# PhotonOnAStick-V3.net
KiCad netlist of a schematic drawn in EAGLE
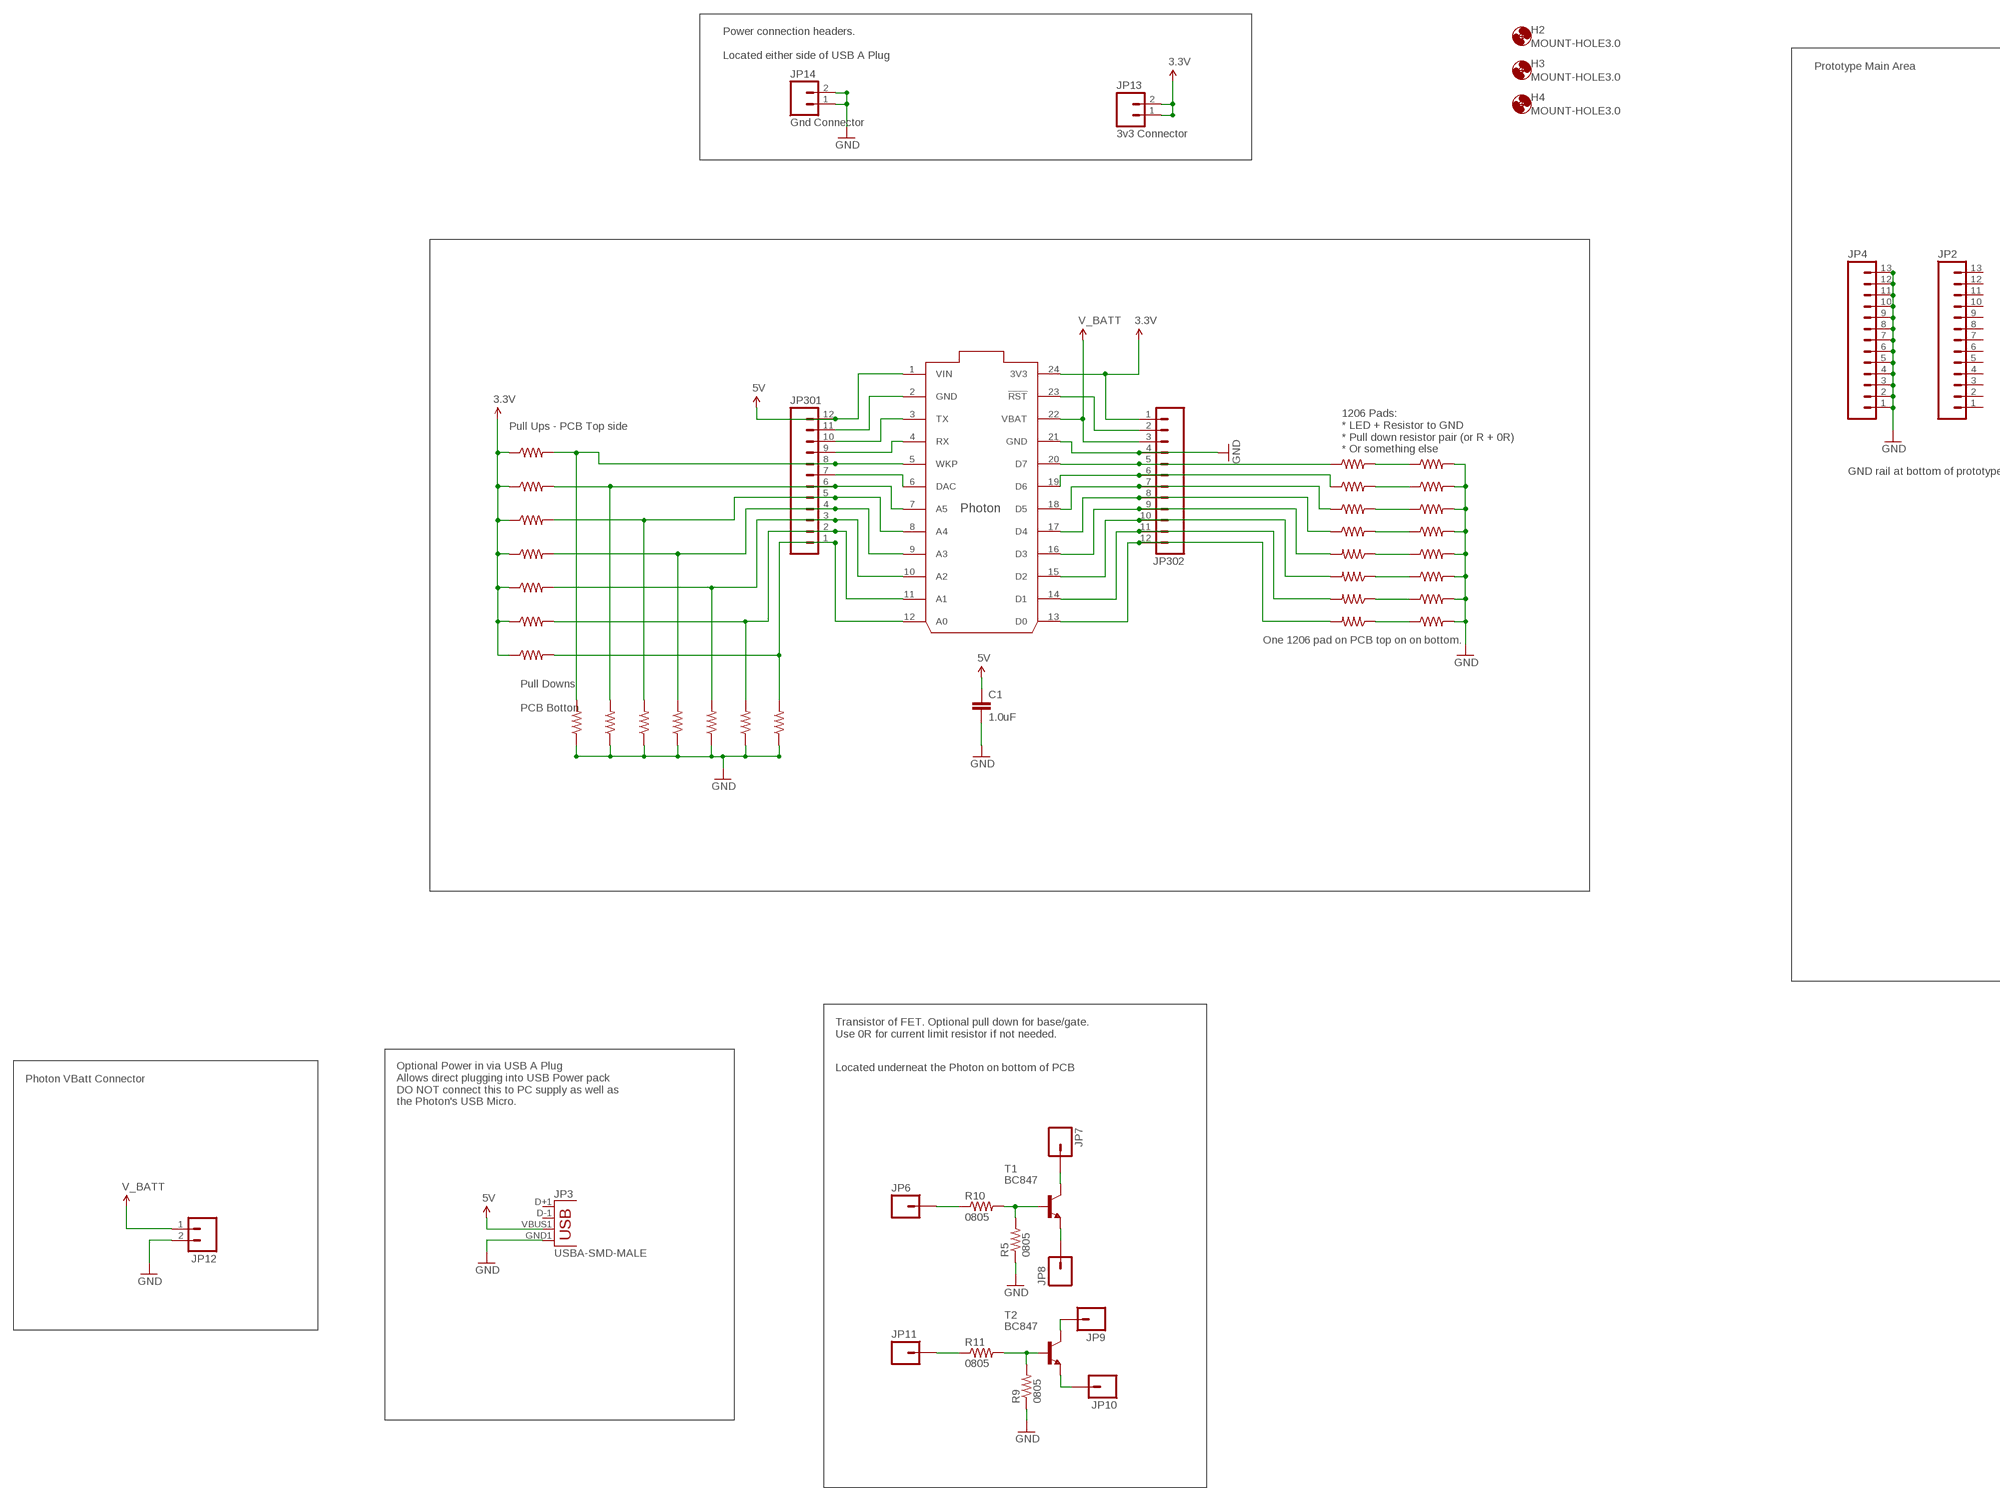
[diagram p0: schematic, sheet 1, part 1 of 2]
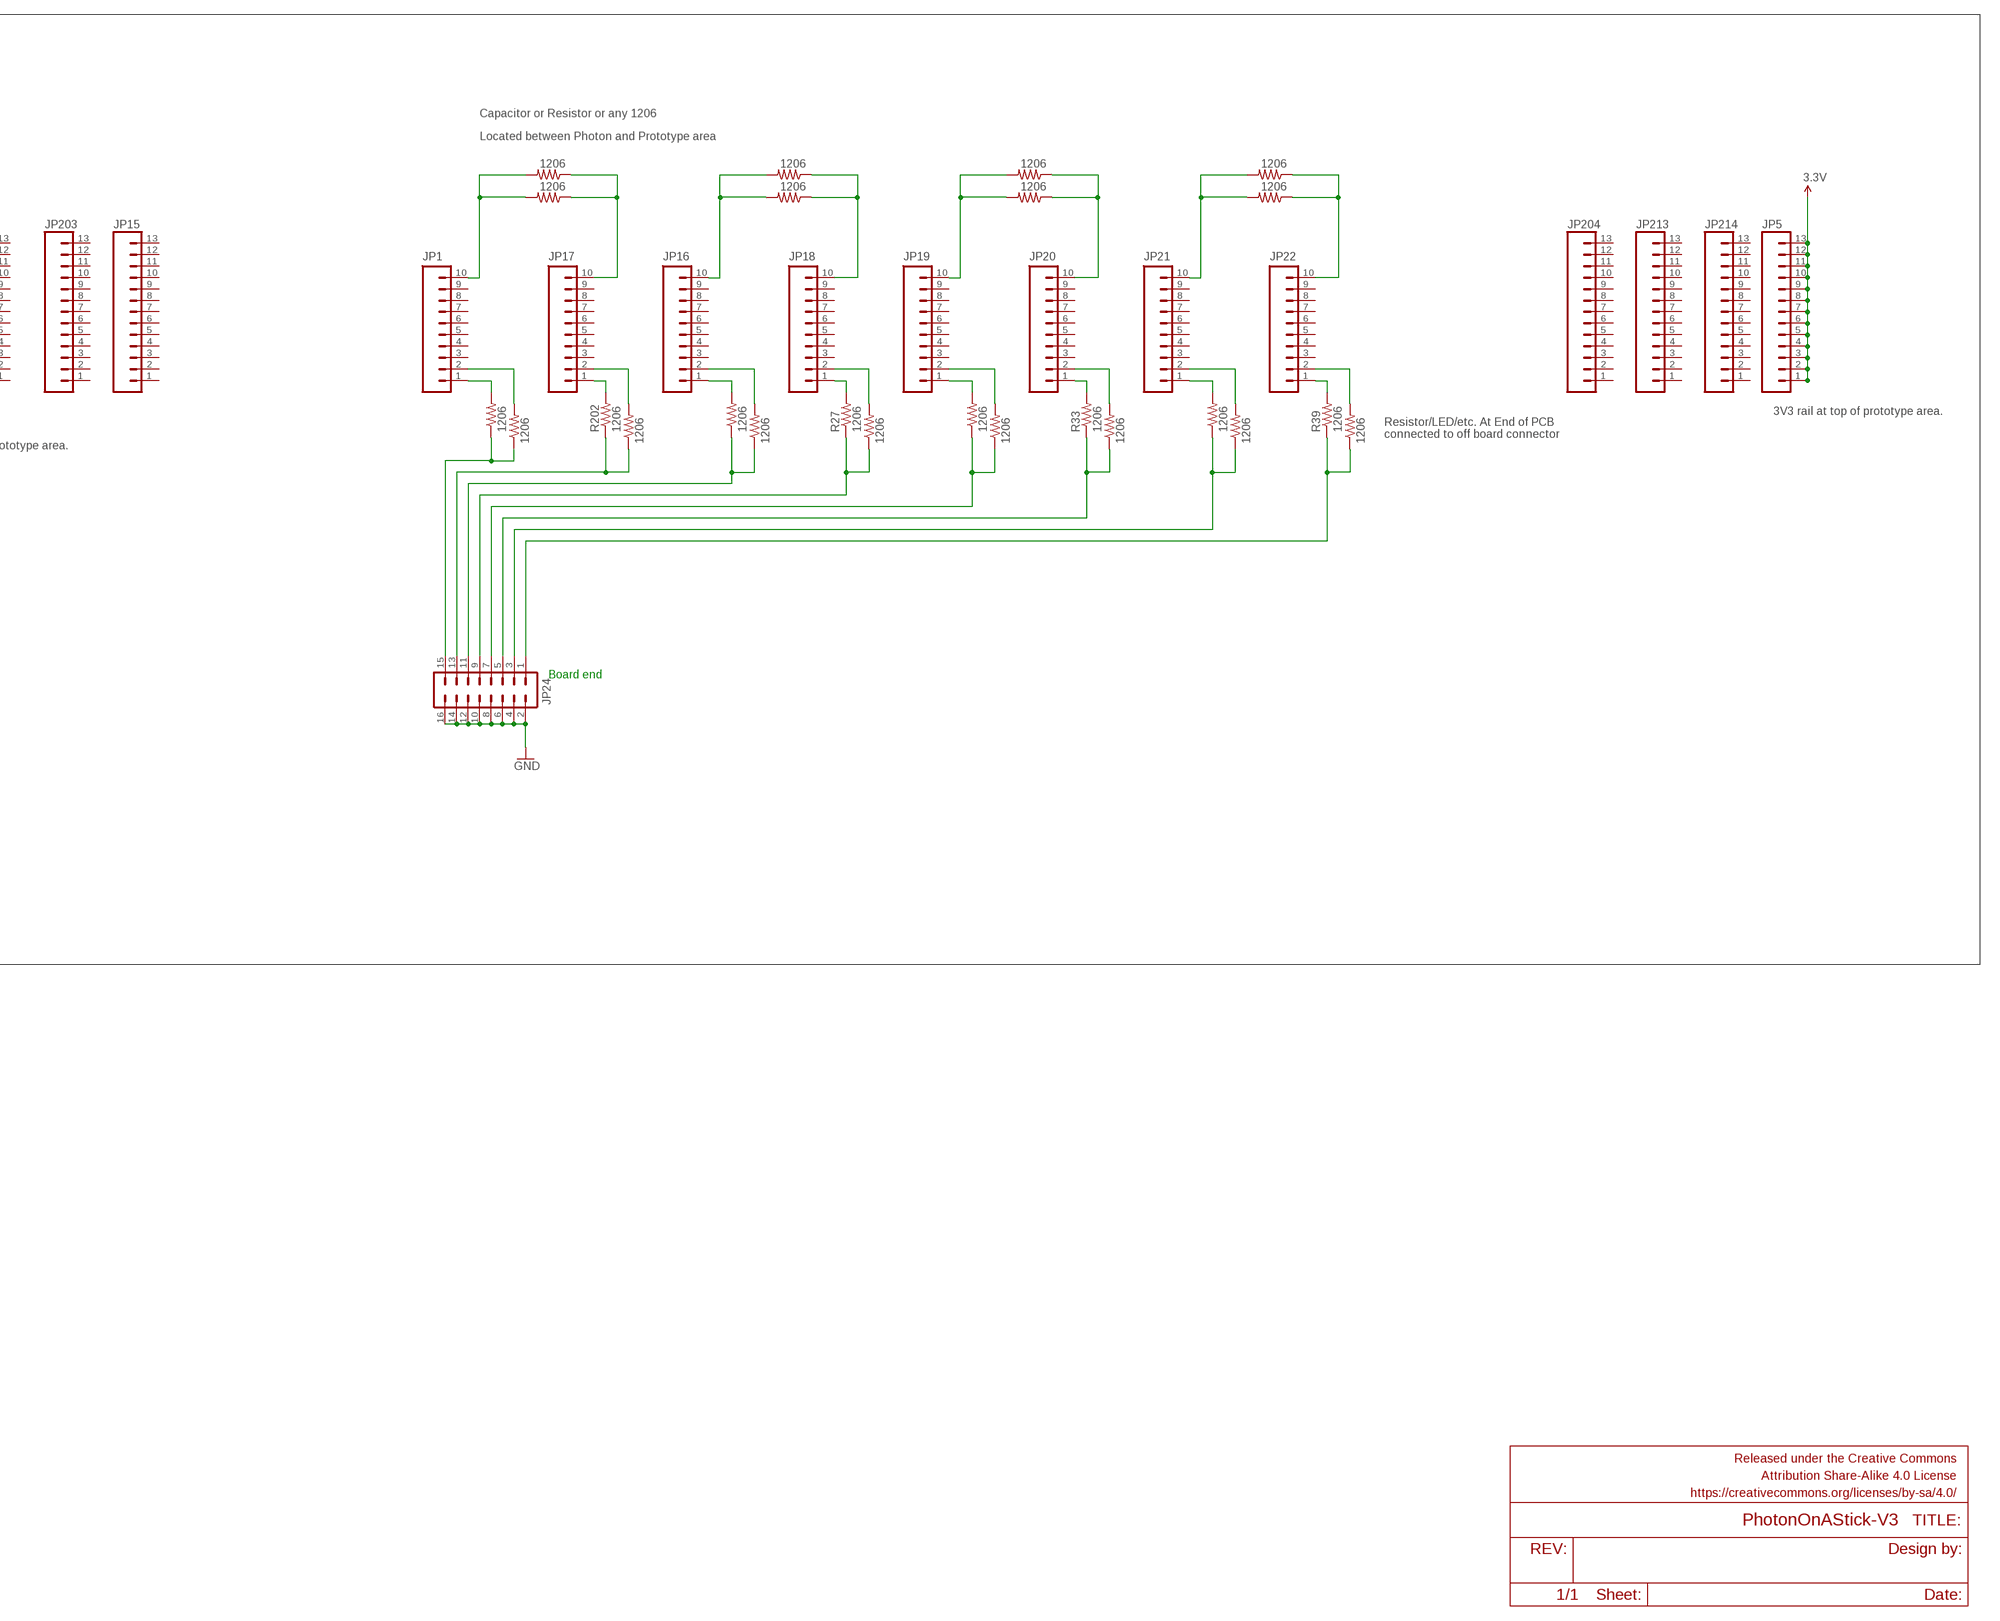
[diagram p1: schematic, sheet 1, part 2 of 2]

(export (version "E")
  (design (tool "Eeschema 10.0.6"))
  (components
    (comp (ref "C1")
      (value "1.0uF")
      (footprint "eagle-import:0805-CAP")
      (libsource (lib "eagle-import") (part "1.0UF-25V-+80/-20(0805){dblquote}"))
    )
    (comp (ref "FRAME1")
      (value "FRAME-LEDGER")
      (footprint "eagle-import:CREATIVE_COMMONS")
      (libsource (lib "eagle-import") (part "FRAME-LEDGER"))
    )
    (comp (ref "H2")
      (value "MOUNT-HOLE3.0")
      (footprint "eagle-import:3,0")
      (libsource (lib "eagle-import") (part "MOUNT-HOLE3.0"))
    )
    (comp (ref "H3")
      (value "MOUNT-HOLE3.0")
      (footprint "eagle-import:3,0")
      (libsource (lib "eagle-import") (part "MOUNT-HOLE3.0"))
    )
    (comp (ref "H4")
      (value "MOUNT-HOLE3.0")
      (footprint "eagle-import:3,0")
      (libsource (lib "eagle-import") (part "MOUNT-HOLE3.0"))
    )
    (comp (ref "IC1")
      (value "PHOTON_WITH_HEADERS")
      (footprint "eagle-import:PHOTON")
      (libsource (lib "eagle-import") (part "PHOTON_WITH_HEADERS"))
    )
    (comp (ref "JP1")
      (value "M10SILK_FEMALE_PTH")
      (footprint "eagle-import:1X10")
      (libsource (lib "eagle-import") (part "M10SILK_FEMALE_PTH"))
    )
    (comp (ref "JP2")
      (value "M13")
      (footprint "eagle-import:1X13")
      (libsource (lib "eagle-import") (part "M13"))
    )
    (comp (ref "JP3")
      (value "USBA-SMD-MALE")
      (footprint "eagle-import:USB-A-SMT-MALE")
      (libsource (lib "eagle-import") (part "USBA-SMD-MALE"))
    )
    (comp (ref "JP4")
      (value "M13")
      (footprint "eagle-import:1X13")
      (libsource (lib "eagle-import") (part "M13"))
    )
    (comp (ref "JP5")
      (value "M13")
      (footprint "eagle-import:1X13")
      (libsource (lib "eagle-import") (part "M13"))
    )
    (comp (ref "JP6")
      (value "M01PTH")
      (footprint "eagle-import:1X01")
      (libsource (lib "eagle-import") (part "M01PTH"))
    )
    (comp (ref "JP7")
      (value "M01PTH")
      (footprint "eagle-import:1X01")
      (libsource (lib "eagle-import") (part "M01PTH"))
    )
    (comp (ref "JP8")
      (value "M01PTH")
      (footprint "eagle-import:1X01")
      (libsource (lib "eagle-import") (part "M01PTH"))
    )
    (comp (ref "JP9")
      (value "M01PTH")
      (footprint "eagle-import:1X01")
      (libsource (lib "eagle-import") (part "M01PTH"))
    )
    (comp (ref "JP10")
      (value "M01PTH")
      (footprint "eagle-import:1X01")
      (libsource (lib "eagle-import") (part "M01PTH"))
    )
    (comp (ref "JP11")
      (value "M01PTH")
      (footprint "eagle-import:1X01")
      (libsource (lib "eagle-import") (part "M01PTH"))
    )
    (comp (ref "JP12")
      (value "M02JST-PTH-2")
      (footprint "eagle-import:JST-2-PTH")
      (libsource (lib "eagle-import") (part "M02JST-PTH-2"))
    )
    (comp (ref "JP13")
      (value "3v3 Connector")
      (footprint "eagle-import:1X02")
      (libsource (lib "eagle-import") (part "M02PTH"))
    )
    (comp (ref "JP14")
      (value "Gnd Connector")
      (footprint "eagle-import:1X02")
      (libsource (lib "eagle-import") (part "M02PTH"))
    )
    (comp (ref "JP15")
      (value "M13")
      (footprint "eagle-import:1X13")
      (libsource (lib "eagle-import") (part "M13"))
    )
    (comp (ref "JP16")
      (value "M10SILK_FEMALE_PTH")
      (footprint "eagle-import:1X10")
      (libsource (lib "eagle-import") (part "M10SILK_FEMALE_PTH"))
    )
    (comp (ref "JP17")
      (value "M10SILK_FEMALE_PTH")
      (footprint "eagle-import:1X10")
      (libsource (lib "eagle-import") (part "M10SILK_FEMALE_PTH"))
    )
    (comp (ref "JP18")
      (value "M10SILK_FEMALE_PTH")
      (footprint "eagle-import:1X10")
      (libsource (lib "eagle-import") (part "M10SILK_FEMALE_PTH"))
    )
    (comp (ref "JP19")
      (value "M10SILK_FEMALE_PTH")
      (footprint "eagle-import:1X10")
      (libsource (lib "eagle-import") (part "M10SILK_FEMALE_PTH"))
    )
    (comp (ref "JP20")
      (value "M10SILK_FEMALE_PTH")
      (footprint "eagle-import:1X10")
      (libsource (lib "eagle-import") (part "M10SILK_FEMALE_PTH"))
    )
    (comp (ref "JP21")
      (value "M10SILK_FEMALE_PTH")
      (footprint "eagle-import:1X10")
      (libsource (lib "eagle-import") (part "M10SILK_FEMALE_PTH"))
    )
    (comp (ref "JP22")
      (value "M10SILK_FEMALE_PTH")
      (footprint "eagle-import:1X10")
      (libsource (lib "eagle-import") (part "M10SILK_FEMALE_PTH"))
    )
    (comp (ref "JP24")
      (value "M08X2")
      (footprint "eagle-import:2X8")
      (libsource (lib "eagle-import") (part "M08X2"))
    )
    (comp (ref "JP203")
      (value "M13")
      (footprint "eagle-import:1X13")
      (libsource (lib "eagle-import") (part "M13"))
    )
    (comp (ref "JP204")
      (value "M13")
      (footprint "eagle-import:1X13")
      (libsource (lib "eagle-import") (part "M13"))
    )
    (comp (ref "JP213")
      (value "M13")
      (footprint "eagle-import:1X13")
      (libsource (lib "eagle-import") (part "M13"))
    )
    (comp (ref "JP214")
      (value "M13")
      (footprint "eagle-import:1X13")
      (libsource (lib "eagle-import") (part "M13"))
    )
    (comp (ref "JP301")
      (value "M12PTH")
      (footprint "eagle-import:1X12")
      (libsource (lib "eagle-import") (part "M12PTH"))
    )
    (comp (ref "JP302")
      (value "M12PTH")
      (footprint "eagle-import:1X12")
      (libsource (lib "eagle-import") (part "M12PTH"))
    )
    (comp (ref "R1")
      (value "1206")
      (footprint "eagle-import:1206")
      (libsource (lib "eagle-import") (part "RESISTOR1206"))
    )
    (comp (ref "R2")
      (value "1206")
      (footprint "eagle-import:1206")
      (libsource (lib "eagle-import") (part "RESISTOR1206"))
    )
    (comp (ref "R3")
      (value "1206")
      (footprint "eagle-import:1206")
      (libsource (lib "eagle-import") (part "RESISTOR1206"))
    )
    (comp (ref "R4")
      (value "1206")
      (footprint "eagle-import:1206")
      (libsource (lib "eagle-import") (part "RESISTOR1206"))
    )
    (comp (ref "R5")
      (value "0805")
      (footprint "eagle-import:0805")
      (libsource (lib "eagle-import") (part "RESISTOR0805-RES"))
    )
    (comp (ref "R6")
      (value "1206")
      (footprint "eagle-import:1206")
      (libsource (lib "eagle-import") (part "RESISTOR1206"))
    )
    (comp (ref "R7")
      (value "1206")
      (footprint "eagle-import:1206")
      (libsource (lib "eagle-import") (part "RESISTOR1206"))
    )
    (comp (ref "R8")
      (value "1206")
      (footprint "eagle-import:1206")
      (libsource (lib "eagle-import") (part "RESISTOR1206"))
    )
    (comp (ref "R9")
      (value "0805")
      (footprint "eagle-import:0805")
      (libsource (lib "eagle-import") (part "RESISTOR0805-RES"))
    )
    (comp (ref "R10")
      (value "0805")
      (footprint "eagle-import:0805")
      (libsource (lib "eagle-import") (part "RESISTOR0805-RES"))
    )
    (comp (ref "R11")
      (value "0805")
      (footprint "eagle-import:0805")
      (libsource (lib "eagle-import") (part "RESISTOR0805-RES"))
    )
    (comp (ref "R12")
      (value "1206")
      (footprint "eagle-import:1206")
      (libsource (lib "eagle-import") (part "RESISTOR1206"))
    )
    (comp (ref "R13")
      (value "1206")
      (footprint "eagle-import:1206")
      (libsource (lib "eagle-import") (part "RESISTOR1206"))
    )
    (comp (ref "R14")
      (value "1206")
      (footprint "eagle-import:1206")
      (libsource (lib "eagle-import") (part "RESISTOR1206"))
    )
    (comp (ref "R15")
      (value "1206")
      (footprint "eagle-import:1206")
      (libsource (lib "eagle-import") (part "RESISTOR1206"))
    )
    (comp (ref "R16")
      (value "1206")
      (footprint "eagle-import:1206")
      (libsource (lib "eagle-import") (part "RESISTOR1206"))
    )
    (comp (ref "R17")
      (value "1206")
      (footprint "eagle-import:1206")
      (libsource (lib "eagle-import") (part "RESISTOR1206"))
    )
    (comp (ref "R18")
      (value "1206")
      (footprint "eagle-import:1206")
      (libsource (lib "eagle-import") (part "RESISTOR1206"))
    )
    (comp (ref "R19")
      (value "1206")
      (footprint "eagle-import:1206")
      (libsource (lib "eagle-import") (part "RESISTOR1206"))
    )
    (comp (ref "R20")
      (value "1206")
      (footprint "eagle-import:1206")
      (libsource (lib "eagle-import") (part "RESISTOR1206"))
    )
    (comp (ref "R21")
      (value "1206")
      (footprint "eagle-import:1206")
      (libsource (lib "eagle-import") (part "RESISTOR1206"))
    )
    (comp (ref "R22")
      (value "1206")
      (footprint "eagle-import:1206")
      (libsource (lib "eagle-import") (part "RESISTOR1206"))
    )
    (comp (ref "R23")
      (value "1206")
      (footprint "eagle-import:1206")
      (libsource (lib "eagle-import") (part "RESISTOR1206"))
    )
    (comp (ref "R24")
      (value "1206")
      (footprint "eagle-import:1206")
      (libsource (lib "eagle-import") (part "RESISTOR1206"))
    )
    (comp (ref "R25")
      (value "1206")
      (footprint "eagle-import:1206")
      (libsource (lib "eagle-import") (part "RESISTOR1206"))
    )
    (comp (ref "R26")
      (value "1206")
      (footprint "eagle-import:1206")
      (libsource (lib "eagle-import") (part "RESISTOR1206"))
    )
    (comp (ref "R27")
      (value "1206")
      (footprint "eagle-import:1206")
      (libsource (lib "eagle-import") (part "RESISTOR1206"))
    )
    (comp (ref "R28")
      (value "1206")
      (footprint "eagle-import:1206")
      (libsource (lib "eagle-import") (part "RESISTOR1206"))
    )
    (comp (ref "R29")
      (value "1206")
      (footprint "eagle-import:1206")
      (libsource (lib "eagle-import") (part "RESISTOR1206"))
    )
    (comp (ref "R30")
      (value "1206")
      (footprint "eagle-import:1206")
      (libsource (lib "eagle-import") (part "RESISTOR1206"))
    )
    (comp (ref "R31")
      (value "1206")
      (footprint "eagle-import:1206")
      (libsource (lib "eagle-import") (part "RESISTOR1206"))
    )
    (comp (ref "R32")
      (value "1206")
      (footprint "eagle-import:1206")
      (libsource (lib "eagle-import") (part "RESISTOR1206"))
    )
    (comp (ref "R33")
      (value "1206")
      (footprint "eagle-import:1206")
      (libsource (lib "eagle-import") (part "RESISTOR1206"))
    )
    (comp (ref "R34")
      (value "1206")
      (footprint "eagle-import:1206")
      (libsource (lib "eagle-import") (part "RESISTOR1206"))
    )
    (comp (ref "R35")
      (value "1206")
      (footprint "eagle-import:1206")
      (libsource (lib "eagle-import") (part "RESISTOR1206"))
    )
    (comp (ref "R36")
      (value "1206")
      (footprint "eagle-import:1206")
      (libsource (lib "eagle-import") (part "RESISTOR1206"))
    )
    (comp (ref "R37")
      (value "1206")
      (footprint "eagle-import:1206")
      (libsource (lib "eagle-import") (part "RESISTOR1206"))
    )
    (comp (ref "R38")
      (value "1206")
      (footprint "eagle-import:1206")
      (libsource (lib "eagle-import") (part "RESISTOR1206"))
    )
    (comp (ref "R39")
      (value "1206")
      (footprint "eagle-import:1206")
      (libsource (lib "eagle-import") (part "RESISTOR1206"))
    )
    (comp (ref "R40")
      (value "1206")
      (footprint "eagle-import:1206")
      (libsource (lib "eagle-import") (part "RESISTOR1206"))
    )
    (comp (ref "R41")
      (value "1206")
      (footprint "eagle-import:1206")
      (libsource (lib "eagle-import") (part "RESISTOR1206"))
    )
    (comp (ref "R42")
      (value "1206")
      (footprint "eagle-import:1206")
      (libsource (lib "eagle-import") (part "RESISTOR1206"))
    )
    (comp (ref "R43")
      (value "1206")
      (footprint "eagle-import:1206")
      (libsource (lib "eagle-import") (part "RESISTOR1206"))
    )
    (comp (ref "R44")
      (value "1206")
      (footprint "eagle-import:1206")
      (libsource (lib "eagle-import") (part "RESISTOR1206"))
    )
    (comp (ref "R201")
      (value "1206")
      (footprint "eagle-import:1206")
      (libsource (lib "eagle-import") (part "RESISTOR1206"))
    )
    (comp (ref "R202")
      (value "1206")
      (footprint "eagle-import:1206")
      (libsource (lib "eagle-import") (part "RESISTOR1206"))
    )
    (comp (ref "R313")
      (value "1206")
      (footprint "eagle-import:1206")
      (libsource (lib "eagle-import") (part "RESISTOR1206"))
    )
    (comp (ref "R314")
      (value "1206")
      (footprint "eagle-import:1206")
      (libsource (lib "eagle-import") (part "RESISTOR1206"))
    )
    (comp (ref "R315")
      (value "1206")
      (footprint "eagle-import:1206")
      (libsource (lib "eagle-import") (part "RESISTOR1206"))
    )
    (comp (ref "R316")
      (value "1206")
      (footprint "eagle-import:1206")
      (libsource (lib "eagle-import") (part "RESISTOR1206"))
    )
    (comp (ref "R317")
      (value "1206")
      (footprint "eagle-import:1206")
      (libsource (lib "eagle-import") (part "RESISTOR1206"))
    )
    (comp (ref "R318")
      (value "1206")
      (footprint "eagle-import:1206")
      (libsource (lib "eagle-import") (part "RESISTOR1206"))
    )
    (comp (ref "R319")
      (value "1206")
      (footprint "eagle-import:1206")
      (libsource (lib "eagle-import") (part "RESISTOR1206"))
    )
    (comp (ref "R320")
      (value "1206")
      (footprint "eagle-import:1206")
      (libsource (lib "eagle-import") (part "RESISTOR1206"))
    )
    (comp (ref "R410")
      (value "1206")
      (footprint "eagle-import:1206")
      (libsource (lib "eagle-import") (part "RESISTOR1206"))
    )
    (comp (ref "R411")
      (value "1206")
      (footprint "eagle-import:1206")
      (libsource (lib "eagle-import") (part "RESISTOR1206"))
    )
    (comp (ref "R412")
      (value "1206")
      (footprint "eagle-import:1206")
      (libsource (lib "eagle-import") (part "RESISTOR1206"))
    )
    (comp (ref "R413")
      (value "1206")
      (footprint "eagle-import:1206")
      (libsource (lib "eagle-import") (part "RESISTOR1206"))
    )
    (comp (ref "T1")
      (value "BC847")
      (footprint "eagle-import:SOT23")
      (libsource (lib "eagle-import") (part "BC847"))
    )
    (comp (ref "T2")
      (value "BC847")
      (footprint "eagle-import:SOT23")
      (libsource (lib "eagle-import") (part "BC847"))
    )
  )
  (nets
    (net (code "1") (name "3.3V") (class "Default")
      (node (ref "IC1") (pin "24") (pinfunction "3V3_24") (pintype "power_in"))
      (node (ref "JP13") (pin "1") (pinfunction "1_1") (pintype "passive"))
      (node (ref "JP13") (pin "2") (pinfunction "2_2") (pintype "passive"))
      (node (ref "JP302") (pin "1") (pinfunction "1_1") (pintype "passive"))
      (node (ref "JP5") (pin "1") (pinfunction "1_1") (pintype "passive"))
      (node (ref "JP5") (pin "10") (pinfunction "10_10") (pintype "passive"))
      (node (ref "JP5") (pin "11") (pinfunction "11_11") (pintype "passive"))
      (node (ref "JP5") (pin "12") (pinfunction "12_12") (pintype "passive"))
      (node (ref "JP5") (pin "13") (pinfunction "13_13") (pintype "passive"))
      (node (ref "JP5") (pin "2") (pinfunction "2_2") (pintype "passive"))
      (node (ref "JP5") (pin "3") (pinfunction "3_3") (pintype "passive"))
      (node (ref "JP5") (pin "4") (pinfunction "4_4") (pintype "passive"))
      (node (ref "JP5") (pin "5") (pinfunction "5_5") (pintype "passive"))
      (node (ref "JP5") (pin "6") (pinfunction "6_6") (pintype "passive"))
      (node (ref "JP5") (pin "7") (pinfunction "7_7") (pintype "passive"))
      (node (ref "JP5") (pin "8") (pinfunction "8_8") (pintype "passive"))
      (node (ref "JP5") (pin "9") (pinfunction "9_9") (pintype "passive"))
      (node (ref "R1") (pin "1") (pinfunction "1_1") (pintype "passive"))
      (node (ref "R12") (pin "1") (pinfunction "1_1") (pintype "passive"))
      (node (ref "R2") (pin "1") (pinfunction "1_1") (pintype "passive"))
      (node (ref "R3") (pin "1") (pinfunction "1_1") (pintype "passive"))
      (node (ref "R4") (pin "1") (pinfunction "1_1") (pintype "passive"))
      (node (ref "R6") (pin "1") (pinfunction "1_1") (pintype "passive"))
      (node (ref "R7") (pin "1") (pinfunction "1_1") (pintype "passive"))
    )
    (net (code "2") (name "5V") (class "Default")
      (node (ref "C1") (pin "1") (pinfunction "1_1") (pintype "passive"))
      (node (ref "IC1") (pin "1") (pinfunction "VIN_1") (pintype "power_in"))
      (node (ref "JP3") (pin "VBUS1") (pinfunction "VBUS_VBUS1") (pintype "bidirectional"))
      (node (ref "JP301") (pin "12") (pinfunction "12_12") (pintype "passive"))
    )
    (net (code "3") (name "GND") (class "Default")
      (node (ref "C1") (pin "2") (pinfunction "2_2") (pintype "passive"))
      (node (ref "IC1") (pin "2") (pinfunction "GND_2") (pintype "power_in"))
      (node (ref "IC1") (pin "21") (pinfunction "GND_21") (pintype "power_in"))
      (node (ref "JP12") (pin "2") (pinfunction "2_2") (pintype "passive"))
      (node (ref "JP14") (pin "1") (pinfunction "1_1") (pintype "passive"))
      (node (ref "JP14") (pin "2") (pinfunction "2_2") (pintype "passive"))
      (node (ref "JP24") (pin "10") (pinfunction "10_10") (pintype "passive"))
      (node (ref "JP24") (pin "12") (pinfunction "12_12") (pintype "passive"))
      (node (ref "JP24") (pin "14") (pinfunction "14_14") (pintype "passive"))
      (node (ref "JP24") (pin "16") (pinfunction "16_16") (pintype "passive"))
      (node (ref "JP24") (pin "2") (pinfunction "2_2") (pintype "passive"))
      (node (ref "JP24") (pin "4") (pinfunction "4_4") (pintype "passive"))
      (node (ref "JP24") (pin "6") (pinfunction "6_6") (pintype "passive"))
      (node (ref "JP24") (pin "8") (pinfunction "8_8") (pintype "passive"))
      (node (ref "JP3") (pin "GND1") (pinfunction "GND_GND1") (pintype "bidirectional"))
      (node (ref "JP301") (pin "11") (pinfunction "11_11") (pintype "passive"))
      (node (ref "JP302") (pin "4") (pinfunction "4_4") (pintype "passive"))
      (node (ref "JP4") (pin "1") (pinfunction "1_1") (pintype "passive"))
      (node (ref "JP4") (pin "10") (pinfunction "10_10") (pintype "passive"))
      (node (ref "JP4") (pin "11") (pinfunction "11_11") (pintype "passive"))
      (node (ref "JP4") (pin "12") (pinfunction "12_12") (pintype "passive"))
      (node (ref "JP4") (pin "13") (pinfunction "13_13") (pintype "passive"))
      (node (ref "JP4") (pin "2") (pinfunction "2_2") (pintype "passive"))
      (node (ref "JP4") (pin "3") (pinfunction "3_3") (pintype "passive"))
      (node (ref "JP4") (pin "4") (pinfunction "4_4") (pintype "passive"))
      (node (ref "JP4") (pin "5") (pinfunction "5_5") (pintype "passive"))
      (node (ref "JP4") (pin "6") (pinfunction "6_6") (pintype "passive"))
      (node (ref "JP4") (pin "7") (pinfunction "7_7") (pintype "passive"))
      (node (ref "JP4") (pin "8") (pinfunction "8_8") (pintype "passive"))
      (node (ref "JP4") (pin "9") (pinfunction "9_9") (pintype "passive"))
      (node (ref "R13") (pin "1") (pinfunction "1_1") (pintype "passive"))
      (node (ref "R14") (pin "1") (pinfunction "1_1") (pintype "passive"))
      (node (ref "R15") (pin "2") (pinfunction "2_2") (pintype "passive"))
      (node (ref "R16") (pin "2") (pinfunction "2_2") (pintype "passive"))
      (node (ref "R17") (pin "2") (pinfunction "2_2") (pintype "passive"))
      (node (ref "R18") (pin "2") (pinfunction "2_2") (pintype "passive"))
      (node (ref "R19") (pin "1") (pinfunction "1_1") (pintype "passive"))
      (node (ref "R20") (pin "1") (pinfunction "1_1") (pintype "passive"))
      (node (ref "R21") (pin "1") (pinfunction "1_1") (pintype "passive"))
      (node (ref "R22") (pin "1") (pinfunction "1_1") (pintype "passive"))
      (node (ref "R410") (pin "2") (pinfunction "2_2") (pintype "passive"))
      (node (ref "R411") (pin "2") (pinfunction "2_2") (pintype "passive"))
      (node (ref "R412") (pin "2") (pinfunction "2_2") (pintype "passive"))
      (node (ref "R413") (pin "2") (pinfunction "2_2") (pintype "passive"))
      (node (ref "R5") (pin "1") (pinfunction "1_1") (pintype "passive"))
      (node (ref "R8") (pin "1") (pinfunction "1_1") (pintype "passive"))
      (node (ref "R9") (pin "1") (pinfunction "1_1") (pintype "passive"))
    )
    (net (code "4") (name "Net-(IC1-A0)") (class "Default")
      (node (ref "IC1") (pin "12") (pinfunction "A0_12") (pintype "bidirectional"))
      (node (ref "JP301") (pin "1") (pinfunction "1_1") (pintype "passive"))
      (node (ref "R22") (pin "2") (pinfunction "2_2") (pintype "passive"))
      (node (ref "R7") (pin "2") (pinfunction "2_2") (pintype "passive"))
    )
    (net (code "5") (name "Net-(IC1-A1)") (class "Default")
      (node (ref "IC1") (pin "11") (pinfunction "A1_11") (pintype "bidirectional"))
      (node (ref "JP301") (pin "2") (pinfunction "2_2") (pintype "passive"))
      (node (ref "R21") (pin "2") (pinfunction "2_2") (pintype "passive"))
      (node (ref "R6") (pin "2") (pinfunction "2_2") (pintype "passive"))
    )
    (net (code "6") (name "Net-(IC1-A2)") (class "Default")
      (node (ref "IC1") (pin "10") (pinfunction "A2_10") (pintype "bidirectional"))
      (node (ref "JP301") (pin "3") (pinfunction "3_3") (pintype "passive"))
      (node (ref "R20") (pin "2") (pinfunction "2_2") (pintype "passive"))
      (node (ref "R4") (pin "2") (pinfunction "2_2") (pintype "passive"))
    )
    (net (code "7") (name "Net-(IC1-A3)") (class "Default")
      (node (ref "IC1") (pin "9") (pinfunction "A3_9") (pintype "bidirectional"))
      (node (ref "JP301") (pin "4") (pinfunction "4_4") (pintype "passive"))
      (node (ref "R19") (pin "2") (pinfunction "2_2") (pintype "passive"))
      (node (ref "R3") (pin "2") (pinfunction "2_2") (pintype "passive"))
    )
    (net (code "8") (name "Net-(IC1-A4)") (class "Default")
      (node (ref "IC1") (pin "8") (pinfunction "A4_8") (pintype "bidirectional"))
      (node (ref "JP301") (pin "5") (pinfunction "5_5") (pintype "passive"))
      (node (ref "R14") (pin "2") (pinfunction "2_2") (pintype "passive"))
      (node (ref "R2") (pin "2") (pinfunction "2_2") (pintype "passive"))
    )
    (net (code "9") (name "Net-(IC1-A5)") (class "Default")
      (node (ref "IC1") (pin "7") (pinfunction "A5_7") (pintype "bidirectional"))
      (node (ref "JP301") (pin "6") (pinfunction "6_6") (pintype "passive"))
      (node (ref "R1") (pin "2") (pinfunction "2_2") (pintype "passive"))
      (node (ref "R13") (pin "2") (pinfunction "2_2") (pintype "passive"))
    )
    (net (code "10") (name "Net-(IC1-D0)") (class "Default")
      (node (ref "IC1") (pin "13") (pinfunction "D0_13") (pintype "bidirectional"))
      (node (ref "JP302") (pin "12") (pinfunction "12_12") (pintype "passive"))
      (node (ref "R313") (pin "2") (pinfunction "2_2") (pintype "passive"))
    )
    (net (code "11") (name "Net-(IC1-D1)") (class "Default")
      (node (ref "IC1") (pin "14") (pinfunction "D1_14") (pintype "bidirectional"))
      (node (ref "JP302") (pin "11") (pinfunction "11_11") (pintype "passive"))
      (node (ref "R314") (pin "2") (pinfunction "2_2") (pintype "passive"))
    )
    (net (code "12") (name "Net-(IC1-D2)") (class "Default")
      (node (ref "IC1") (pin "15") (pinfunction "D2_15") (pintype "bidirectional"))
      (node (ref "JP302") (pin "10") (pinfunction "10_10") (pintype "passive"))
      (node (ref "R315") (pin "2") (pinfunction "2_2") (pintype "passive"))
    )
    (net (code "13") (name "Net-(IC1-D3)") (class "Default")
      (node (ref "IC1") (pin "16") (pinfunction "D3_16") (pintype "bidirectional"))
      (node (ref "JP302") (pin "9") (pinfunction "9_9") (pintype "passive"))
      (node (ref "R316") (pin "2") (pinfunction "2_2") (pintype "passive"))
    )
    (net (code "14") (name "Net-(IC1-D4)") (class "Default")
      (node (ref "IC1") (pin "17") (pinfunction "D4_17") (pintype "bidirectional"))
      (node (ref "JP302") (pin "8") (pinfunction "8_8") (pintype "passive"))
      (node (ref "R317") (pin "1") (pinfunction "1_1") (pintype "passive"))
    )
    (net (code "15") (name "Net-(IC1-D5)") (class "Default")
      (node (ref "IC1") (pin "18") (pinfunction "D5_18") (pintype "bidirectional"))
      (node (ref "JP302") (pin "7") (pinfunction "7_7") (pintype "passive"))
      (node (ref "R318") (pin "1") (pinfunction "1_1") (pintype "passive"))
    )
    (net (code "16") (name "Net-(IC1-D6)") (class "Default")
      (node (ref "IC1") (pin "19") (pinfunction "D6_19") (pintype "bidirectional"))
      (node (ref "JP302") (pin "6") (pinfunction "6_6") (pintype "passive"))
      (node (ref "R319") (pin "1") (pinfunction "1_1") (pintype "passive"))
    )
    (net (code "17") (name "Net-(IC1-D7)") (class "Default")
      (node (ref "IC1") (pin "20") (pinfunction "D7_20") (pintype "bidirectional"))
      (node (ref "JP302") (pin "5") (pinfunction "5_5") (pintype "passive"))
      (node (ref "R320") (pin "1") (pinfunction "1_1") (pintype "passive"))
    )
    (net (code "18") (name "Net-(IC1-DAC)") (class "Default")
      (node (ref "IC1") (pin "6") (pinfunction "DAC_6") (pintype "bidirectional"))
      (node (ref "JP301") (pin "7") (pinfunction "7_7") (pintype "passive"))
    )
    (net (code "19") (name "Net-(IC1-RX)") (class "Default")
      (node (ref "IC1") (pin "4") (pinfunction "RX_4") (pintype "bidirectional"))
      (node (ref "JP301") (pin "9") (pinfunction "9_9") (pintype "passive"))
    )
    (net (code "20") (name "Net-(IC1-TX)") (class "Default")
      (node (ref "IC1") (pin "3") (pinfunction "TX_3") (pintype "bidirectional"))
      (node (ref "JP301") (pin "10") (pinfunction "10_10") (pintype "passive"))
    )
    (net (code "21") (name "Net-(IC1-WKP)") (class "Default")
      (node (ref "IC1") (pin "5") (pinfunction "WKP_5") (pintype "bidirectional"))
      (node (ref "JP301") (pin "8") (pinfunction "8_8") (pintype "passive"))
      (node (ref "R12") (pin "2") (pinfunction "2_2") (pintype "passive"))
      (node (ref "R8") (pin "2") (pinfunction "2_2") (pintype "passive"))
    )
    (net (code "22") (name "Net-(IC1-~{RST})") (class "Default")
      (node (ref "IC1") (pin "23") (pinfunction "~{RST}_23") (pintype "bidirectional"))
      (node (ref "JP302") (pin "2") (pinfunction "2_2") (pintype "passive"))
    )
    (net (code "23") (name "Net-(JP1-Pad1)") (class "Default")
      (node (ref "JP1") (pin "1") (pinfunction "1_1") (pintype "passive"))
      (node (ref "R201") (pin "2") (pinfunction "2_2") (pintype "passive"))
    )
    (net (code "24") (name "Net-(JP1-Pad2)") (class "Default")
      (node (ref "JP1") (pin "2") (pinfunction "2_2") (pintype "passive"))
      (node (ref "R23") (pin "2") (pinfunction "2_2") (pintype "passive"))
    )
    (net (code "25") (name "Net-(JP1-Pad10)") (class "Default")
      (node (ref "JP1") (pin "10") (pinfunction "10_10") (pintype "passive"))
      (node (ref "R24") (pin "2") (pinfunction "2_2") (pintype "passive"))
      (node (ref "R25") (pin "2") (pinfunction "2_2") (pintype "passive"))
    )
    (net (code "26") (name "Net-(JP6-Pad1)") (class "Default")
      (node (ref "JP6") (pin "1") (pinfunction "1_1") (pintype "passive"))
      (node (ref "R10") (pin "1") (pinfunction "1_1") (pintype "passive"))
    )
    (net (code "27") (name "Net-(JP11-Pad1)") (class "Default")
      (node (ref "JP11") (pin "1") (pinfunction "1_1") (pintype "passive"))
      (node (ref "R11") (pin "1") (pinfunction "1_1") (pintype "passive"))
    )
    (net (code "28") (name "Net-(JP16-Pad1)") (class "Default")
      (node (ref "JP16") (pin "1") (pinfunction "1_1") (pintype "passive"))
      (node (ref "R28") (pin "2") (pinfunction "2_2") (pintype "passive"))
    )
    (net (code "29") (name "Net-(JP16-Pad2)") (class "Default")
      (node (ref "JP16") (pin "2") (pinfunction "2_2") (pintype "passive"))
      (node (ref "R29") (pin "2") (pinfunction "2_2") (pintype "passive"))
    )
    (net (code "30") (name "Net-(JP16-Pad10)") (class "Default")
      (node (ref "JP16") (pin "10") (pinfunction "10_10") (pintype "passive"))
      (node (ref "R30") (pin "2") (pinfunction "2_2") (pintype "passive"))
      (node (ref "R31") (pin "2") (pinfunction "2_2") (pintype "passive"))
    )
    (net (code "31") (name "Net-(JP17-Pad1)") (class "Default")
      (node (ref "JP17") (pin "1") (pinfunction "1_1") (pintype "passive"))
      (node (ref "R202") (pin "2") (pinfunction "2_2") (pintype "passive"))
    )
    (net (code "32") (name "Net-(JP17-Pad2)") (class "Default")
      (node (ref "JP17") (pin "2") (pinfunction "2_2") (pintype "passive"))
      (node (ref "R26") (pin "2") (pinfunction "2_2") (pintype "passive"))
    )
    (net (code "33") (name "Net-(JP17-Pad10)") (class "Default")
      (node (ref "JP17") (pin "10") (pinfunction "10_10") (pintype "passive"))
      (node (ref "R24") (pin "1") (pinfunction "1_1") (pintype "passive"))
      (node (ref "R25") (pin "1") (pinfunction "1_1") (pintype "passive"))
    )
    (net (code "34") (name "Net-(JP18-Pad1)") (class "Default")
      (node (ref "JP18") (pin "1") (pinfunction "1_1") (pintype "passive"))
      (node (ref "R27") (pin "2") (pinfunction "2_2") (pintype "passive"))
    )
    (net (code "35") (name "Net-(JP18-Pad2)") (class "Default")
      (node (ref "JP18") (pin "2") (pinfunction "2_2") (pintype "passive"))
      (node (ref "R32") (pin "2") (pinfunction "2_2") (pintype "passive"))
    )
    (net (code "36") (name "Net-(JP18-Pad10)") (class "Default")
      (node (ref "JP18") (pin "10") (pinfunction "10_10") (pintype "passive"))
      (node (ref "R30") (pin "1") (pinfunction "1_1") (pintype "passive"))
      (node (ref "R31") (pin "1") (pinfunction "1_1") (pintype "passive"))
    )
    (net (code "37") (name "Net-(JP19-Pad1)") (class "Default")
      (node (ref "JP19") (pin "1") (pinfunction "1_1") (pintype "passive"))
      (node (ref "R34") (pin "2") (pinfunction "2_2") (pintype "passive"))
    )
    (net (code "38") (name "Net-(JP19-Pad2)") (class "Default")
      (node (ref "JP19") (pin "2") (pinfunction "2_2") (pintype "passive"))
      (node (ref "R35") (pin "2") (pinfunction "2_2") (pintype "passive"))
    )
    (net (code "39") (name "Net-(JP19-Pad10)") (class "Default")
      (node (ref "JP19") (pin "10") (pinfunction "10_10") (pintype "passive"))
      (node (ref "R36") (pin "2") (pinfunction "2_2") (pintype "passive"))
      (node (ref "R37") (pin "2") (pinfunction "2_2") (pintype "passive"))
    )
    (net (code "40") (name "Net-(JP20-Pad1)") (class "Default")
      (node (ref "JP20") (pin "1") (pinfunction "1_1") (pintype "passive"))
      (node (ref "R33") (pin "2") (pinfunction "2_2") (pintype "passive"))
    )
    (net (code "41") (name "Net-(JP20-Pad2)") (class "Default")
      (node (ref "JP20") (pin "2") (pinfunction "2_2") (pintype "passive"))
      (node (ref "R38") (pin "2") (pinfunction "2_2") (pintype "passive"))
    )
    (net (code "42") (name "Net-(JP20-Pad10)") (class "Default")
      (node (ref "JP20") (pin "10") (pinfunction "10_10") (pintype "passive"))
      (node (ref "R36") (pin "1") (pinfunction "1_1") (pintype "passive"))
      (node (ref "R37") (pin "1") (pinfunction "1_1") (pintype "passive"))
    )
    (net (code "43") (name "Net-(JP21-Pad1)") (class "Default")
      (node (ref "JP21") (pin "1") (pinfunction "1_1") (pintype "passive"))
      (node (ref "R40") (pin "2") (pinfunction "2_2") (pintype "passive"))
    )
    (net (code "44") (name "Net-(JP21-Pad2)") (class "Default")
      (node (ref "JP21") (pin "2") (pinfunction "2_2") (pintype "passive"))
      (node (ref "R41") (pin "2") (pinfunction "2_2") (pintype "passive"))
    )
    (net (code "45") (name "Net-(JP21-Pad10)") (class "Default")
      (node (ref "JP21") (pin "10") (pinfunction "10_10") (pintype "passive"))
      (node (ref "R42") (pin "2") (pinfunction "2_2") (pintype "passive"))
      (node (ref "R43") (pin "2") (pinfunction "2_2") (pintype "passive"))
    )
    (net (code "46") (name "Net-(JP22-Pad1)") (class "Default")
      (node (ref "JP22") (pin "1") (pinfunction "1_1") (pintype "passive"))
      (node (ref "R39") (pin "2") (pinfunction "2_2") (pintype "passive"))
    )
    (net (code "47") (name "Net-(JP22-Pad2)") (class "Default")
      (node (ref "JP22") (pin "2") (pinfunction "2_2") (pintype "passive"))
      (node (ref "R44") (pin "2") (pinfunction "2_2") (pintype "passive"))
    )
    (net (code "48") (name "Net-(JP22-Pad10)") (class "Default")
      (node (ref "JP22") (pin "10") (pinfunction "10_10") (pintype "passive"))
      (node (ref "R42") (pin "1") (pinfunction "1_1") (pintype "passive"))
      (node (ref "R43") (pin "1") (pinfunction "1_1") (pintype "passive"))
    )
    (net (code "49") (name "Net-(JP24-Pad1)") (class "Default")
      (node (ref "JP24") (pin "1") (pinfunction "1_1") (pintype "passive"))
      (node (ref "R39") (pin "1") (pinfunction "1_1") (pintype "passive"))
      (node (ref "R44") (pin "1") (pinfunction "1_1") (pintype "passive"))
    )
    (net (code "50") (name "Net-(JP24-Pad3)") (class "Default")
      (node (ref "JP24") (pin "3") (pinfunction "3_3") (pintype "passive"))
      (node (ref "R40") (pin "1") (pinfunction "1_1") (pintype "passive"))
      (node (ref "R41") (pin "1") (pinfunction "1_1") (pintype "passive"))
    )
    (net (code "51") (name "Net-(JP24-Pad5)") (class "Default")
      (node (ref "JP24") (pin "5") (pinfunction "5_5") (pintype "passive"))
      (node (ref "R33") (pin "1") (pinfunction "1_1") (pintype "passive"))
      (node (ref "R38") (pin "1") (pinfunction "1_1") (pintype "passive"))
    )
    (net (code "52") (name "Net-(JP24-Pad7)") (class "Default")
      (node (ref "JP24") (pin "7") (pinfunction "7_7") (pintype "passive"))
      (node (ref "R34") (pin "1") (pinfunction "1_1") (pintype "passive"))
      (node (ref "R35") (pin "1") (pinfunction "1_1") (pintype "passive"))
    )
    (net (code "53") (name "Net-(JP24-Pad9)") (class "Default")
      (node (ref "JP24") (pin "9") (pinfunction "9_9") (pintype "passive"))
      (node (ref "R27") (pin "1") (pinfunction "1_1") (pintype "passive"))
      (node (ref "R32") (pin "1") (pinfunction "1_1") (pintype "passive"))
    )
    (net (code "54") (name "Net-(JP24-Pad11)") (class "Default")
      (node (ref "JP24") (pin "11") (pinfunction "11_11") (pintype "passive"))
      (node (ref "R28") (pin "1") (pinfunction "1_1") (pintype "passive"))
      (node (ref "R29") (pin "1") (pinfunction "1_1") (pintype "passive"))
    )
    (net (code "55") (name "Net-(JP24-Pad13)") (class "Default")
      (node (ref "JP24") (pin "13") (pinfunction "13_13") (pintype "passive"))
      (node (ref "R202") (pin "1") (pinfunction "1_1") (pintype "passive"))
      (node (ref "R26") (pin "1") (pinfunction "1_1") (pintype "passive"))
    )
    (net (code "56") (name "Net-(JP24-Pad15)") (class "Default")
      (node (ref "JP24") (pin "15") (pinfunction "15_15") (pintype "passive"))
      (node (ref "R201") (pin "1") (pinfunction "1_1") (pintype "passive"))
      (node (ref "R23") (pin "1") (pinfunction "1_1") (pintype "passive"))
    )
    (net (code "57") (name "Net-(R15-Pad1)") (class "Default")
      (node (ref "R15") (pin "1") (pinfunction "1_1") (pintype "passive"))
      (node (ref "R316") (pin "1") (pinfunction "1_1") (pintype "passive"))
    )
    (net (code "58") (name "Net-(R16-Pad1)") (class "Default")
      (node (ref "R16") (pin "1") (pinfunction "1_1") (pintype "passive"))
      (node (ref "R315") (pin "1") (pinfunction "1_1") (pintype "passive"))
    )
    (net (code "59") (name "Net-(R17-Pad1)") (class "Default")
      (node (ref "R17") (pin "1") (pinfunction "1_1") (pintype "passive"))
      (node (ref "R314") (pin "1") (pinfunction "1_1") (pintype "passive"))
    )
    (net (code "60") (name "Net-(R18-Pad1)") (class "Default")
      (node (ref "R18") (pin "1") (pinfunction "1_1") (pintype "passive"))
      (node (ref "R313") (pin "1") (pinfunction "1_1") (pintype "passive"))
    )
    (net (code "61") (name "Net-(R317-Pad2)") (class "Default")
      (node (ref "R317") (pin "2") (pinfunction "2_2") (pintype "passive"))
      (node (ref "R413") (pin "1") (pinfunction "1_1") (pintype "passive"))
    )
    (net (code "62") (name "Net-(R318-Pad2)") (class "Default")
      (node (ref "R318") (pin "2") (pinfunction "2_2") (pintype "passive"))
      (node (ref "R412") (pin "1") (pinfunction "1_1") (pintype "passive"))
    )
    (net (code "63") (name "Net-(R319-Pad2)") (class "Default")
      (node (ref "R319") (pin "2") (pinfunction "2_2") (pintype "passive"))
      (node (ref "R411") (pin "1") (pinfunction "1_1") (pintype "passive"))
    )
    (net (code "64") (name "Net-(R320-Pad2)") (class "Default")
      (node (ref "R320") (pin "2") (pinfunction "2_2") (pintype "passive"))
      (node (ref "R410") (pin "1") (pinfunction "1_1") (pintype "passive"))
    )
    (net (code "65") (name "Net-(T1-B)") (class "Default")
      (node (ref "R10") (pin "2") (pinfunction "2_2") (pintype "passive"))
      (node (ref "R5") (pin "2") (pinfunction "2_2") (pintype "passive"))
      (node (ref "T1") (pin "1") (pinfunction "B_1") (pintype "passive"))
    )
    (net (code "66") (name "Net-(T1-C)") (class "Default")
      (node (ref "JP7") (pin "1") (pinfunction "1_1") (pintype "passive"))
      (node (ref "T1") (pin "3") (pinfunction "C_3") (pintype "passive"))
    )
    (net (code "67") (name "Net-(T1-E)") (class "Default")
      (node (ref "JP8") (pin "1") (pinfunction "1_1") (pintype "passive"))
      (node (ref "T1") (pin "2") (pinfunction "E_2") (pintype "passive"))
    )
    (net (code "68") (name "Net-(T2-B)") (class "Default")
      (node (ref "R11") (pin "2") (pinfunction "2_2") (pintype "passive"))
      (node (ref "R9") (pin "2") (pinfunction "2_2") (pintype "passive"))
      (node (ref "T2") (pin "1") (pinfunction "B_1") (pintype "passive"))
    )
    (net (code "69") (name "Net-(T2-C)") (class "Default")
      (node (ref "JP9") (pin "1") (pinfunction "1_1") (pintype "passive"))
      (node (ref "T2") (pin "3") (pinfunction "C_3") (pintype "passive"))
    )
    (net (code "70") (name "Net-(T2-E)") (class "Default")
      (node (ref "JP10") (pin "1") (pinfunction "1_1") (pintype "passive"))
      (node (ref "T2") (pin "2") (pinfunction "E_2") (pintype "passive"))
    )
    (net (code "71") (name "V_BATT") (class "Default")
      (node (ref "IC1") (pin "22") (pinfunction "VBAT_22") (pintype "power_in"))
      (node (ref "JP12") (pin "1") (pinfunction "1_1") (pintype "passive"))
      (node (ref "JP302") (pin "3") (pinfunction "3_3") (pintype "passive"))
    )
    (net (code "72") (name "unconnected-(JP1-Pad3)") (class "Default")
      (node (ref "JP1") (pin "3") (pinfunction "3_3") (pintype "passive"))
    )
    (net (code "73") (name "unconnected-(JP1-Pad4)") (class "Default")
      (node (ref "JP1") (pin "4") (pinfunction "4_4") (pintype "passive"))
    )
    (net (code "74") (name "unconnected-(JP1-Pad5)") (class "Default")
      (node (ref "JP1") (pin "5") (pinfunction "5_5") (pintype "passive"))
    )
    (net (code "75") (name "unconnected-(JP1-Pad6)") (class "Default")
      (node (ref "JP1") (pin "6") (pinfunction "6_6") (pintype "passive"))
    )
    (net (code "76") (name "unconnected-(JP1-Pad7)") (class "Default")
      (node (ref "JP1") (pin "7") (pinfunction "7_7") (pintype "passive"))
    )
    (net (code "77") (name "unconnected-(JP1-Pad8)") (class "Default")
      (node (ref "JP1") (pin "8") (pinfunction "8_8") (pintype "passive"))
    )
    (net (code "78") (name "unconnected-(JP1-Pad9)") (class "Default")
      (node (ref "JP1") (pin "9") (pinfunction "9_9") (pintype "passive"))
    )
    (net (code "79") (name "unconnected-(JP2-Pad1)") (class "Default")
      (node (ref "JP2") (pin "1") (pinfunction "1_1") (pintype "passive"))
    )
    (net (code "80") (name "unconnected-(JP2-Pad2)") (class "Default")
      (node (ref "JP2") (pin "2") (pinfunction "2_2") (pintype "passive"))
    )
    (net (code "81") (name "unconnected-(JP2-Pad3)") (class "Default")
      (node (ref "JP2") (pin "3") (pinfunction "3_3") (pintype "passive"))
    )
    (net (code "82") (name "unconnected-(JP2-Pad4)") (class "Default")
      (node (ref "JP2") (pin "4") (pinfunction "4_4") (pintype "passive"))
    )
    (net (code "83") (name "unconnected-(JP2-Pad5)") (class "Default")
      (node (ref "JP2") (pin "5") (pinfunction "5_5") (pintype "passive"))
    )
    (net (code "84") (name "unconnected-(JP2-Pad6)") (class "Default")
      (node (ref "JP2") (pin "6") (pinfunction "6_6") (pintype "passive"))
    )
    (net (code "85") (name "unconnected-(JP2-Pad7)") (class "Default")
      (node (ref "JP2") (pin "7") (pinfunction "7_7") (pintype "passive"))
    )
    (net (code "86") (name "unconnected-(JP2-Pad8)") (class "Default")
      (node (ref "JP2") (pin "8") (pinfunction "8_8") (pintype "passive"))
    )
    (net (code "87") (name "unconnected-(JP2-Pad9)") (class "Default")
      (node (ref "JP2") (pin "9") (pinfunction "9_9") (pintype "passive"))
    )
    (net (code "88") (name "unconnected-(JP2-Pad10)") (class "Default")
      (node (ref "JP2") (pin "10") (pinfunction "10_10") (pintype "passive"))
    )
    (net (code "89") (name "unconnected-(JP2-Pad11)") (class "Default")
      (node (ref "JP2") (pin "11") (pinfunction "11_11") (pintype "passive"))
    )
    (net (code "90") (name "unconnected-(JP2-Pad12)") (class "Default")
      (node (ref "JP2") (pin "12") (pinfunction "12_12") (pintype "passive"))
    )
    (net (code "91") (name "unconnected-(JP2-Pad13)") (class "Default")
      (node (ref "JP2") (pin "13") (pinfunction "13_13") (pintype "passive"))
    )
    (net (code "92") (name "unconnected-(JP3-D+-PadD+1)") (class "Default")
      (node (ref "JP3") (pin "D+1") (pinfunction "D+_D+1") (pintype "bidirectional"))
    )
    (net (code "93") (name "unconnected-(JP3-D--PadD-1)") (class "Default")
      (node (ref "JP3") (pin "D-1") (pinfunction "D-_D-1") (pintype "bidirectional"))
    )
    (net (code "94") (name "unconnected-(JP15-Pad1)") (class "Default")
      (node (ref "JP15") (pin "1") (pinfunction "1_1") (pintype "passive"))
    )
    (net (code "95") (name "unconnected-(JP15-Pad2)") (class "Default")
      (node (ref "JP15") (pin "2") (pinfunction "2_2") (pintype "passive"))
    )
    (net (code "96") (name "unconnected-(JP15-Pad3)") (class "Default")
      (node (ref "JP15") (pin "3") (pinfunction "3_3") (pintype "passive"))
    )
    (net (code "97") (name "unconnected-(JP15-Pad4)") (class "Default")
      (node (ref "JP15") (pin "4") (pinfunction "4_4") (pintype "passive"))
    )
    (net (code "98") (name "unconnected-(JP15-Pad5)") (class "Default")
      (node (ref "JP15") (pin "5") (pinfunction "5_5") (pintype "passive"))
    )
    (net (code "99") (name "unconnected-(JP15-Pad6)") (class "Default")
      (node (ref "JP15") (pin "6") (pinfunction "6_6") (pintype "passive"))
    )
    (net (code "100") (name "unconnected-(JP15-Pad7)") (class "Default")
      (node (ref "JP15") (pin "7") (pinfunction "7_7") (pintype "passive"))
    )
    (net (code "101") (name "unconnected-(JP15-Pad8)") (class "Default")
      (node (ref "JP15") (pin "8") (pinfunction "8_8") (pintype "passive"))
    )
    (net (code "102") (name "unconnected-(JP15-Pad9)") (class "Default")
      (node (ref "JP15") (pin "9") (pinfunction "9_9") (pintype "passive"))
    )
    (net (code "103") (name "unconnected-(JP15-Pad10)") (class "Default")
      (node (ref "JP15") (pin "10") (pinfunction "10_10") (pintype "passive"))
    )
    (net (code "104") (name "unconnected-(JP15-Pad11)") (class "Default")
      (node (ref "JP15") (pin "11") (pinfunction "11_11") (pintype "passive"))
    )
    (net (code "105") (name "unconnected-(JP15-Pad12)") (class "Default")
      (node (ref "JP15") (pin "12") (pinfunction "12_12") (pintype "passive"))
    )
    (net (code "106") (name "unconnected-(JP15-Pad13)") (class "Default")
      (node (ref "JP15") (pin "13") (pinfunction "13_13") (pintype "passive"))
    )
    (net (code "107") (name "unconnected-(JP16-Pad3)") (class "Default")
      (node (ref "JP16") (pin "3") (pinfunction "3_3") (pintype "passive"))
    )
    (net (code "108") (name "unconnected-(JP16-Pad4)") (class "Default")
      (node (ref "JP16") (pin "4") (pinfunction "4_4") (pintype "passive"))
    )
    (net (code "109") (name "unconnected-(JP16-Pad5)") (class "Default")
      (node (ref "JP16") (pin "5") (pinfunction "5_5") (pintype "passive"))
    )
    (net (code "110") (name "unconnected-(JP16-Pad6)") (class "Default")
      (node (ref "JP16") (pin "6") (pinfunction "6_6") (pintype "passive"))
    )
    (net (code "111") (name "unconnected-(JP16-Pad7)") (class "Default")
      (node (ref "JP16") (pin "7") (pinfunction "7_7") (pintype "passive"))
    )
    (net (code "112") (name "unconnected-(JP16-Pad8)") (class "Default")
      (node (ref "JP16") (pin "8") (pinfunction "8_8") (pintype "passive"))
    )
    (net (code "113") (name "unconnected-(JP16-Pad9)") (class "Default")
      (node (ref "JP16") (pin "9") (pinfunction "9_9") (pintype "passive"))
    )
    (net (code "114") (name "unconnected-(JP17-Pad3)") (class "Default")
      (node (ref "JP17") (pin "3") (pinfunction "3_3") (pintype "passive"))
    )
    (net (code "115") (name "unconnected-(JP17-Pad4)") (class "Default")
      (node (ref "JP17") (pin "4") (pinfunction "4_4") (pintype "passive"))
    )
    (net (code "116") (name "unconnected-(JP17-Pad5)") (class "Default")
      (node (ref "JP17") (pin "5") (pinfunction "5_5") (pintype "passive"))
    )
    (net (code "117") (name "unconnected-(JP17-Pad6)") (class "Default")
      (node (ref "JP17") (pin "6") (pinfunction "6_6") (pintype "passive"))
    )
    (net (code "118") (name "unconnected-(JP17-Pad7)") (class "Default")
      (node (ref "JP17") (pin "7") (pinfunction "7_7") (pintype "passive"))
    )
    (net (code "119") (name "unconnected-(JP17-Pad8)") (class "Default")
      (node (ref "JP17") (pin "8") (pinfunction "8_8") (pintype "passive"))
    )
    (net (code "120") (name "unconnected-(JP17-Pad9)") (class "Default")
      (node (ref "JP17") (pin "9") (pinfunction "9_9") (pintype "passive"))
    )
    (net (code "121") (name "unconnected-(JP18-Pad3)") (class "Default")
      (node (ref "JP18") (pin "3") (pinfunction "3_3") (pintype "passive"))
    )
    (net (code "122") (name "unconnected-(JP18-Pad4)") (class "Default")
      (node (ref "JP18") (pin "4") (pinfunction "4_4") (pintype "passive"))
    )
    (net (code "123") (name "unconnected-(JP18-Pad5)") (class "Default")
      (node (ref "JP18") (pin "5") (pinfunction "5_5") (pintype "passive"))
    )
    (net (code "124") (name "unconnected-(JP18-Pad6)") (class "Default")
      (node (ref "JP18") (pin "6") (pinfunction "6_6") (pintype "passive"))
    )
    (net (code "125") (name "unconnected-(JP18-Pad7)") (class "Default")
      (node (ref "JP18") (pin "7") (pinfunction "7_7") (pintype "passive"))
    )
    (net (code "126") (name "unconnected-(JP18-Pad8)") (class "Default")
      (node (ref "JP18") (pin "8") (pinfunction "8_8") (pintype "passive"))
    )
    (net (code "127") (name "unconnected-(JP18-Pad9)") (class "Default")
      (node (ref "JP18") (pin "9") (pinfunction "9_9") (pintype "passive"))
    )
    (net (code "128") (name "unconnected-(JP19-Pad3)") (class "Default")
      (node (ref "JP19") (pin "3") (pinfunction "3_3") (pintype "passive"))
    )
    (net (code "129") (name "unconnected-(JP19-Pad4)") (class "Default")
      (node (ref "JP19") (pin "4") (pinfunction "4_4") (pintype "passive"))
    )
    (net (code "130") (name "unconnected-(JP19-Pad5)") (class "Default")
      (node (ref "JP19") (pin "5") (pinfunction "5_5") (pintype "passive"))
    )
    (net (code "131") (name "unconnected-(JP19-Pad6)") (class "Default")
      (node (ref "JP19") (pin "6") (pinfunction "6_6") (pintype "passive"))
    )
    (net (code "132") (name "unconnected-(JP19-Pad7)") (class "Default")
      (node (ref "JP19") (pin "7") (pinfunction "7_7") (pintype "passive"))
    )
    (net (code "133") (name "unconnected-(JP19-Pad8)") (class "Default")
      (node (ref "JP19") (pin "8") (pinfunction "8_8") (pintype "passive"))
    )
    (net (code "134") (name "unconnected-(JP19-Pad9)") (class "Default")
      (node (ref "JP19") (pin "9") (pinfunction "9_9") (pintype "passive"))
    )
    (net (code "135") (name "unconnected-(JP20-Pad3)") (class "Default")
      (node (ref "JP20") (pin "3") (pinfunction "3_3") (pintype "passive"))
    )
    (net (code "136") (name "unconnected-(JP20-Pad4)") (class "Default")
      (node (ref "JP20") (pin "4") (pinfunction "4_4") (pintype "passive"))
    )
    (net (code "137") (name "unconnected-(JP20-Pad5)") (class "Default")
      (node (ref "JP20") (pin "5") (pinfunction "5_5") (pintype "passive"))
    )
    (net (code "138") (name "unconnected-(JP20-Pad6)") (class "Default")
      (node (ref "JP20") (pin "6") (pinfunction "6_6") (pintype "passive"))
    )
    (net (code "139") (name "unconnected-(JP20-Pad7)") (class "Default")
      (node (ref "JP20") (pin "7") (pinfunction "7_7") (pintype "passive"))
    )
    (net (code "140") (name "unconnected-(JP20-Pad8)") (class "Default")
      (node (ref "JP20") (pin "8") (pinfunction "8_8") (pintype "passive"))
    )
    (net (code "141") (name "unconnected-(JP20-Pad9)") (class "Default")
      (node (ref "JP20") (pin "9") (pinfunction "9_9") (pintype "passive"))
    )
    (net (code "142") (name "unconnected-(JP21-Pad3)") (class "Default")
      (node (ref "JP21") (pin "3") (pinfunction "3_3") (pintype "passive"))
    )
    (net (code "143") (name "unconnected-(JP21-Pad4)") (class "Default")
      (node (ref "JP21") (pin "4") (pinfunction "4_4") (pintype "passive"))
    )
    (net (code "144") (name "unconnected-(JP21-Pad5)") (class "Default")
      (node (ref "JP21") (pin "5") (pinfunction "5_5") (pintype "passive"))
    )
    (net (code "145") (name "unconnected-(JP21-Pad6)") (class "Default")
      (node (ref "JP21") (pin "6") (pinfunction "6_6") (pintype "passive"))
    )
    (net (code "146") (name "unconnected-(JP21-Pad7)") (class "Default")
      (node (ref "JP21") (pin "7") (pinfunction "7_7") (pintype "passive"))
    )
    (net (code "147") (name "unconnected-(JP21-Pad8)") (class "Default")
      (node (ref "JP21") (pin "8") (pinfunction "8_8") (pintype "passive"))
    )
    (net (code "148") (name "unconnected-(JP21-Pad9)") (class "Default")
      (node (ref "JP21") (pin "9") (pinfunction "9_9") (pintype "passive"))
    )
    (net (code "149") (name "unconnected-(JP22-Pad3)") (class "Default")
      (node (ref "JP22") (pin "3") (pinfunction "3_3") (pintype "passive"))
    )
    (net (code "150") (name "unconnected-(JP22-Pad4)") (class "Default")
      (node (ref "JP22") (pin "4") (pinfunction "4_4") (pintype "passive"))
    )
    (net (code "151") (name "unconnected-(JP22-Pad5)") (class "Default")
      (node (ref "JP22") (pin "5") (pinfunction "5_5") (pintype "passive"))
    )
    (net (code "152") (name "unconnected-(JP22-Pad6)") (class "Default")
      (node (ref "JP22") (pin "6") (pinfunction "6_6") (pintype "passive"))
    )
    (net (code "153") (name "unconnected-(JP22-Pad7)") (class "Default")
      (node (ref "JP22") (pin "7") (pinfunction "7_7") (pintype "passive"))
    )
    (net (code "154") (name "unconnected-(JP22-Pad8)") (class "Default")
      (node (ref "JP22") (pin "8") (pinfunction "8_8") (pintype "passive"))
    )
    (net (code "155") (name "unconnected-(JP22-Pad9)") (class "Default")
      (node (ref "JP22") (pin "9") (pinfunction "9_9") (pintype "passive"))
    )
    (net (code "156") (name "unconnected-(JP203-Pad1)") (class "Default")
      (node (ref "JP203") (pin "1") (pinfunction "1_1") (pintype "passive"))
    )
    (net (code "157") (name "unconnected-(JP203-Pad2)") (class "Default")
      (node (ref "JP203") (pin "2") (pinfunction "2_2") (pintype "passive"))
    )
    (net (code "158") (name "unconnected-(JP203-Pad3)") (class "Default")
      (node (ref "JP203") (pin "3") (pinfunction "3_3") (pintype "passive"))
    )
    (net (code "159") (name "unconnected-(JP203-Pad4)") (class "Default")
      (node (ref "JP203") (pin "4") (pinfunction "4_4") (pintype "passive"))
    )
    (net (code "160") (name "unconnected-(JP203-Pad5)") (class "Default")
      (node (ref "JP203") (pin "5") (pinfunction "5_5") (pintype "passive"))
    )
    (net (code "161") (name "unconnected-(JP203-Pad6)") (class "Default")
      (node (ref "JP203") (pin "6") (pinfunction "6_6") (pintype "passive"))
    )
    (net (code "162") (name "unconnected-(JP203-Pad7)") (class "Default")
      (node (ref "JP203") (pin "7") (pinfunction "7_7") (pintype "passive"))
    )
    (net (code "163") (name "unconnected-(JP203-Pad8)") (class "Default")
      (node (ref "JP203") (pin "8") (pinfunction "8_8") (pintype "passive"))
    )
    (net (code "164") (name "unconnected-(JP203-Pad9)") (class "Default")
      (node (ref "JP203") (pin "9") (pinfunction "9_9") (pintype "passive"))
    )
    (net (code "165") (name "unconnected-(JP203-Pad10)") (class "Default")
      (node (ref "JP203") (pin "10") (pinfunction "10_10") (pintype "passive"))
    )
    (net (code "166") (name "unconnected-(JP203-Pad11)") (class "Default")
      (node (ref "JP203") (pin "11") (pinfunction "11_11") (pintype "passive"))
    )
    (net (code "167") (name "unconnected-(JP203-Pad12)") (class "Default")
      (node (ref "JP203") (pin "12") (pinfunction "12_12") (pintype "passive"))
    )
    (net (code "168") (name "unconnected-(JP203-Pad13)") (class "Default")
      (node (ref "JP203") (pin "13") (pinfunction "13_13") (pintype "passive"))
    )
    (net (code "169") (name "unconnected-(JP204-Pad1)") (class "Default")
      (node (ref "JP204") (pin "1") (pinfunction "1_1") (pintype "passive"))
    )
    (net (code "170") (name "unconnected-(JP204-Pad2)") (class "Default")
      (node (ref "JP204") (pin "2") (pinfunction "2_2") (pintype "passive"))
    )
    (net (code "171") (name "unconnected-(JP204-Pad3)") (class "Default")
      (node (ref "JP204") (pin "3") (pinfunction "3_3") (pintype "passive"))
    )
    (net (code "172") (name "unconnected-(JP204-Pad4)") (class "Default")
      (node (ref "JP204") (pin "4") (pinfunction "4_4") (pintype "passive"))
    )
    (net (code "173") (name "unconnected-(JP204-Pad5)") (class "Default")
      (node (ref "JP204") (pin "5") (pinfunction "5_5") (pintype "passive"))
    )
    (net (code "174") (name "unconnected-(JP204-Pad6)") (class "Default")
      (node (ref "JP204") (pin "6") (pinfunction "6_6") (pintype "passive"))
    )
    (net (code "175") (name "unconnected-(JP204-Pad7)") (class "Default")
      (node (ref "JP204") (pin "7") (pinfunction "7_7") (pintype "passive"))
    )
    (net (code "176") (name "unconnected-(JP204-Pad8)") (class "Default")
      (node (ref "JP204") (pin "8") (pinfunction "8_8") (pintype "passive"))
    )
    (net (code "177") (name "unconnected-(JP204-Pad9)") (class "Default")
      (node (ref "JP204") (pin "9") (pinfunction "9_9") (pintype "passive"))
    )
    (net (code "178") (name "unconnected-(JP204-Pad10)") (class "Default")
      (node (ref "JP204") (pin "10") (pinfunction "10_10") (pintype "passive"))
    )
    (net (code "179") (name "unconnected-(JP204-Pad11)") (class "Default")
      (node (ref "JP204") (pin "11") (pinfunction "11_11") (pintype "passive"))
    )
    (net (code "180") (name "unconnected-(JP204-Pad12)") (class "Default")
      (node (ref "JP204") (pin "12") (pinfunction "12_12") (pintype "passive"))
    )
    (net (code "181") (name "unconnected-(JP204-Pad13)") (class "Default")
      (node (ref "JP204") (pin "13") (pinfunction "13_13") (pintype "passive"))
    )
    (net (code "182") (name "unconnected-(JP213-Pad1)") (class "Default")
      (node (ref "JP213") (pin "1") (pinfunction "1_1") (pintype "passive"))
    )
    (net (code "183") (name "unconnected-(JP213-Pad2)") (class "Default")
      (node (ref "JP213") (pin "2") (pinfunction "2_2") (pintype "passive"))
    )
    (net (code "184") (name "unconnected-(JP213-Pad3)") (class "Default")
      (node (ref "JP213") (pin "3") (pinfunction "3_3") (pintype "passive"))
    )
    (net (code "185") (name "unconnected-(JP213-Pad4)") (class "Default")
      (node (ref "JP213") (pin "4") (pinfunction "4_4") (pintype "passive"))
    )
    (net (code "186") (name "unconnected-(JP213-Pad5)") (class "Default")
      (node (ref "JP213") (pin "5") (pinfunction "5_5") (pintype "passive"))
    )
    (net (code "187") (name "unconnected-(JP213-Pad6)") (class "Default")
      (node (ref "JP213") (pin "6") (pinfunction "6_6") (pintype "passive"))
    )
    (net (code "188") (name "unconnected-(JP213-Pad7)") (class "Default")
      (node (ref "JP213") (pin "7") (pinfunction "7_7") (pintype "passive"))
    )
    (net (code "189") (name "unconnected-(JP213-Pad8)") (class "Default")
      (node (ref "JP213") (pin "8") (pinfunction "8_8") (pintype "passive"))
    )
    (net (code "190") (name "unconnected-(JP213-Pad9)") (class "Default")
      (node (ref "JP213") (pin "9") (pinfunction "9_9") (pintype "passive"))
    )
    (net (code "191") (name "unconnected-(JP213-Pad10)") (class "Default")
      (node (ref "JP213") (pin "10") (pinfunction "10_10") (pintype "passive"))
    )
    (net (code "192") (name "unconnected-(JP213-Pad11)") (class "Default")
      (node (ref "JP213") (pin "11") (pinfunction "11_11") (pintype "passive"))
    )
    (net (code "193") (name "unconnected-(JP213-Pad12)") (class "Default")
      (node (ref "JP213") (pin "12") (pinfunction "12_12") (pintype "passive"))
    )
    (net (code "194") (name "unconnected-(JP213-Pad13)") (class "Default")
      (node (ref "JP213") (pin "13") (pinfunction "13_13") (pintype "passive"))
    )
    (net (code "195") (name "unconnected-(JP214-Pad1)") (class "Default")
      (node (ref "JP214") (pin "1") (pinfunction "1_1") (pintype "passive"))
    )
    (net (code "196") (name "unconnected-(JP214-Pad2)") (class "Default")
      (node (ref "JP214") (pin "2") (pinfunction "2_2") (pintype "passive"))
    )
    (net (code "197") (name "unconnected-(JP214-Pad3)") (class "Default")
      (node (ref "JP214") (pin "3") (pinfunction "3_3") (pintype "passive"))
    )
    (net (code "198") (name "unconnected-(JP214-Pad4)") (class "Default")
      (node (ref "JP214") (pin "4") (pinfunction "4_4") (pintype "passive"))
    )
    (net (code "199") (name "unconnected-(JP214-Pad5)") (class "Default")
      (node (ref "JP214") (pin "5") (pinfunction "5_5") (pintype "passive"))
    )
    (net (code "200") (name "unconnected-(JP214-Pad6)") (class "Default")
      (node (ref "JP214") (pin "6") (pinfunction "6_6") (pintype "passive"))
    )
    (net (code "201") (name "unconnected-(JP214-Pad7)") (class "Default")
      (node (ref "JP214") (pin "7") (pinfunction "7_7") (pintype "passive"))
    )
    (net (code "202") (name "unconnected-(JP214-Pad8)") (class "Default")
      (node (ref "JP214") (pin "8") (pinfunction "8_8") (pintype "passive"))
    )
    (net (code "203") (name "unconnected-(JP214-Pad9)") (class "Default")
      (node (ref "JP214") (pin "9") (pinfunction "9_9") (pintype "passive"))
    )
    (net (code "204") (name "unconnected-(JP214-Pad10)") (class "Default")
      (node (ref "JP214") (pin "10") (pinfunction "10_10") (pintype "passive"))
    )
    (net (code "205") (name "unconnected-(JP214-Pad11)") (class "Default")
      (node (ref "JP214") (pin "11") (pinfunction "11_11") (pintype "passive"))
    )
    (net (code "206") (name "unconnected-(JP214-Pad12)") (class "Default")
      (node (ref "JP214") (pin "12") (pinfunction "12_12") (pintype "passive"))
    )
    (net (code "207") (name "unconnected-(JP214-Pad13)") (class "Default")
      (node (ref "JP214") (pin "13") (pinfunction "13_13") (pintype "passive"))
    )
  )
)
